# memoryModule.net
KiCad netlist of a schematic drawn in EAGLE
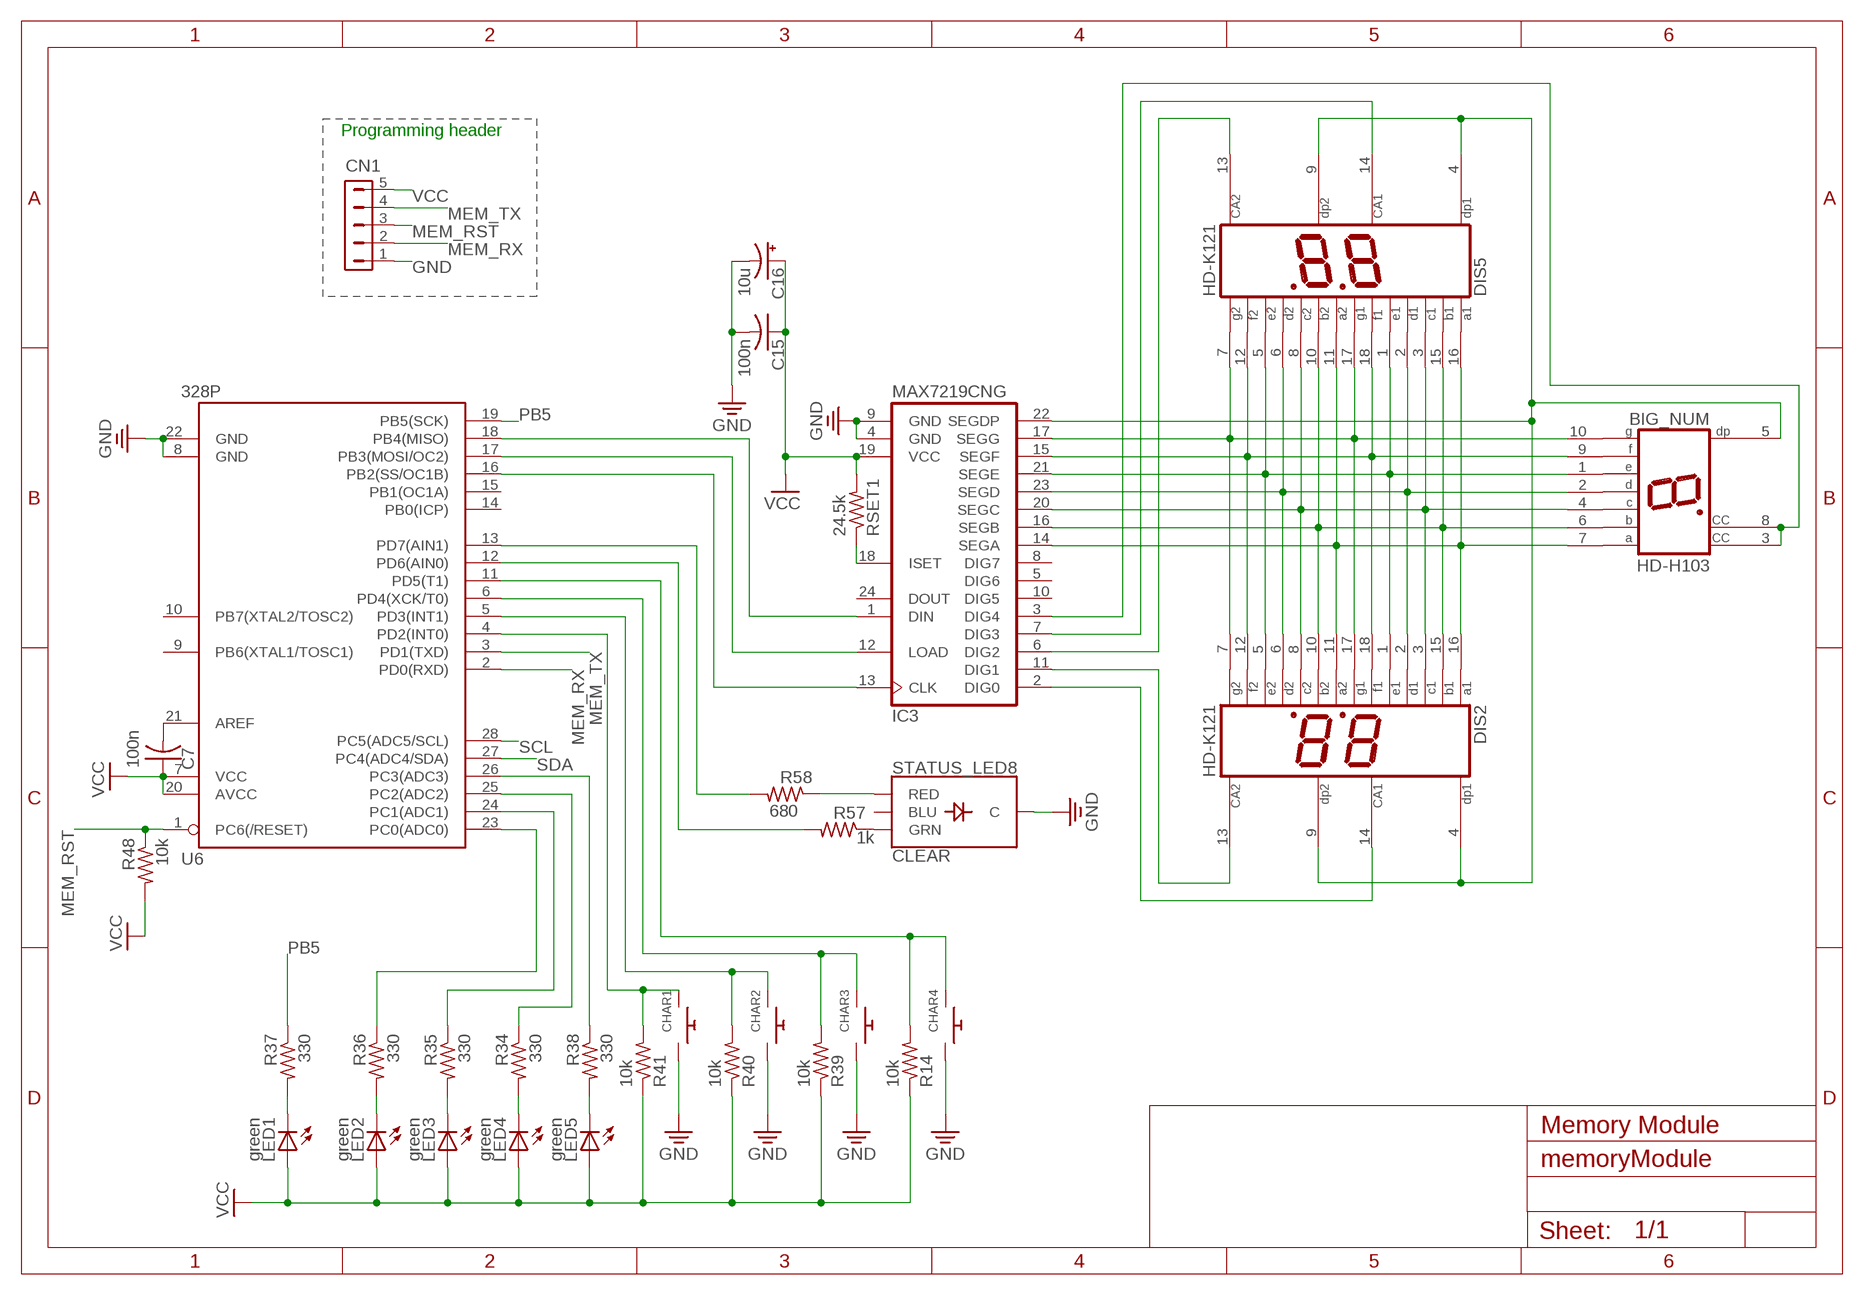
[diagram p0: schematic, sheet 1]

(export (version "E")
  (design (tool "Eeschema 10.0.6"))
  (components
    (comp (ref "BIG_NUM")
      (value "HD-H103")
      (footprint "eagle-import:HDSP-M")
      (libsource (lib "eagle-import") (part "HD-H103"))
    )
    (comp (ref "C7")
      (value "100n")
      (footprint "eagle-import:C025-024X044")
      (libsource (lib "eagle-import") (part "C-US025-024X044"))
    )
    (comp (ref "C15")
      (value "100n")
      (footprint "eagle-import:C025-024X044")
      (libsource (lib "eagle-import") (part "C-US025-024X044"))
    )
    (comp (ref "C16")
      (value "10u")
      (footprint "eagle-import:085CS_1AR")
      (libsource (lib "eagle-import") (part "CPOL-US085CS-1AR"))
    )
    (comp (ref "CHAR1")
      (value "SWITCH_PUSHBUTTONEVQ-PE")
      (footprint "eagle-import:TACT_PANA-EVQ")
      (libsource (lib "eagle-import") (part "SWITCH_PUSHBUTTONEVQ-PE"))
    )
    (comp (ref "CHAR2")
      (value "SWITCH_PUSHBUTTONEVQ-PE")
      (footprint "eagle-import:TACT_PANA-EVQ")
      (libsource (lib "eagle-import") (part "SWITCH_PUSHBUTTONEVQ-PE"))
    )
    (comp (ref "CHAR3")
      (value "SWITCH_PUSHBUTTONEVQ-PE")
      (footprint "eagle-import:TACT_PANA-EVQ")
      (libsource (lib "eagle-import") (part "SWITCH_PUSHBUTTONEVQ-PE"))
    )
    (comp (ref "CHAR4")
      (value "SWITCH_PUSHBUTTONEVQ-PE")
      (footprint "eagle-import:TACT_PANA-EVQ")
      (libsource (lib "eagle-import") (part "SWITCH_PUSHBUTTONEVQ-PE"))
    )
    (comp (ref "CN1")
      (value "HDR-1X5-SIP-100")
      (footprint "eagle-import:SIP-100-5V")
      (libsource (lib "eagle-import") (part "HDR-1X5-SIP-100"))
    )
    (comp (ref "DIS2")
      (value "HD-K121")
      (footprint "eagle-import:HDSP-R")
      (libsource (lib "eagle-import") (part "HD-K121"))
    )
    (comp (ref "DIS5")
      (value "HD-K121")
      (footprint "eagle-import:HDSP-R")
      (libsource (lib "eagle-import") (part "HD-K121"))
    )
    (comp (ref "IC3")
      (value "MAX7219CNG")
      (footprint "eagle-import:DIL24-3")
      (fields (field (name "MF") "MAXIM"))
      (libsource (lib "eagle-import") (part "MAX7219CNG"))
    )
    (comp (ref "LED1")
      (value "green")
      (footprint "eagle-import:LED5MM")
      (libsource (lib "eagle-import") (part "LED5MM"))
    )
    (comp (ref "LED2")
      (value "green")
      (footprint "eagle-import:LED5MM")
      (libsource (lib "eagle-import") (part "LED5MM"))
    )
    (comp (ref "LED3")
      (value "green")
      (footprint "eagle-import:LED5MM")
      (libsource (lib "eagle-import") (part "LED5MM"))
    )
    (comp (ref "LED4")
      (value "green")
      (footprint "eagle-import:LED5MM")
      (libsource (lib "eagle-import") (part "LED5MM"))
    )
    (comp (ref "LED5")
      (value "green")
      (footprint "eagle-import:LED5MM")
      (libsource (lib "eagle-import") (part "LED5MM"))
    )
    (comp (ref "R14")
      (value "10k")
      (footprint "eagle-import:0309_12")
      (libsource (lib "eagle-import") (part "adafruit_420_R-US_0309/12"))
    )
    (comp (ref "R34")
      (value "330")
      (footprint "eagle-import:0309_12")
      (libsource (lib "eagle-import") (part "adafruit_420_R-US_0309/12"))
    )
    (comp (ref "R35")
      (value "330")
      (footprint "eagle-import:0309_12")
      (libsource (lib "eagle-import") (part "adafruit_420_R-US_0309/12"))
    )
    (comp (ref "R36")
      (value "330")
      (footprint "eagle-import:0309_12")
      (libsource (lib "eagle-import") (part "adafruit_420_R-US_0309/12"))
    )
    (comp (ref "R37")
      (value "330")
      (footprint "eagle-import:0309_12")
      (libsource (lib "eagle-import") (part "adafruit_420_R-US_0309/12"))
    )
    (comp (ref "R38")
      (value "330")
      (footprint "eagle-import:0309_12")
      (libsource (lib "eagle-import") (part "adafruit_420_R-US_0309/12"))
    )
    (comp (ref "R39")
      (value "10k")
      (footprint "eagle-import:0309_12")
      (libsource (lib "eagle-import") (part "adafruit_420_R-US_0309/12"))
    )
    (comp (ref "R40")
      (value "10k")
      (footprint "eagle-import:0309_12")
      (libsource (lib "eagle-import") (part "adafruit_420_R-US_0309/12"))
    )
    (comp (ref "R41")
      (value "10k")
      (footprint "eagle-import:0309_12")
      (libsource (lib "eagle-import") (part "adafruit_420_R-US_0309/12"))
    )
    (comp (ref "R48")
      (value "10k")
      (footprint "eagle-import:0309_12")
      (libsource (lib "eagle-import") (part "adafruit_420_R-US_0309/12"))
    )
    (comp (ref "R57")
      (value "1k")
      (footprint "eagle-import:0805-THM")
      (libsource (lib "eagle-import") (part "FLIPFLOP-RES"))
    )
    (comp (ref "R58")
      (value "680")
      (footprint "eagle-import:0805-THM")
      (libsource (lib "eagle-import") (part "FLIPFLOP-RES"))
    )
    (comp (ref "RSET1")
      (value "24.5k")
      (footprint "eagle-import:0204_7")
      (libsource (lib "eagle-import") (part "R-US_0204/7"))
    )
    (comp (ref "STATUS_LED8")
      (value "CLEAR")
      (footprint "eagle-import:LED-RGB-THRU")
      (libsource (lib "eagle-import") (part "LED-RGB-CCCLEAR"))
    )
    (comp (ref "U6")
      (value "328P")
      (footprint "eagle-import:DIP28")
      (libsource (lib "eagle-import") (part "ATMEGA328P_PDIP"))
    )
  )
  (nets
    (net (code "1") (name "/MEM_RST") (class "Default")
      (node (ref "CN1") (pin "3") (pinfunction "3_3") (pintype "passive"))
      (node (ref "R48") (pin "1") (pinfunction "1_1") (pintype "passive"))
      (node (ref "U6") (pin "1") (pinfunction "PC6(/RESET)_1") (pintype "bidirectional"))
    )
    (net (code "2") (name "/MEM_RX") (class "Default")
      (node (ref "CN1") (pin "2") (pinfunction "2_2") (pintype "passive"))
      (node (ref "U6") (pin "2") (pinfunction "PD0(RXD)_2") (pintype "bidirectional"))
    )
    (net (code "3") (name "/MEM_TX") (class "Default")
      (node (ref "CN1") (pin "4") (pinfunction "4_4") (pintype "passive"))
      (node (ref "U6") (pin "3") (pinfunction "PD1(TXD)_3") (pintype "bidirectional"))
    )
    (net (code "4") (name "/N$114") (class "Default")
      (node (ref "R35") (pin "1") (pinfunction "1_1") (pintype "passive"))
      (node (ref "R36") (pin "1") (pinfunction "1_1") (pintype "passive"))
      (node (ref "R38") (pin "1") (pinfunction "1_1") (pintype "passive"))
      (node (ref "U6") (pin "23") (pinfunction "PC0(ADC0)_23") (pintype "bidirectional"))
      (node (ref "U6") (pin "24") (pinfunction "PC1(ADC1)_24") (pintype "bidirectional"))
      (node (ref "U6") (pin "26") (pinfunction "PC3(ADC3)_26") (pintype "bidirectional"))
    )
    (net (code "5") (name "/PB5") (class "Default")
      (node (ref "R37") (pin "1") (pinfunction "1_1") (pintype "passive"))
      (node (ref "U6") (pin "19") (pinfunction "PB5(SCK)_19") (pintype "bidirectional"))
    )
    (net (code "6") (name "/SCL") (class "Default")
      (node (ref "U6") (pin "28") (pinfunction "PC5(ADC5/SCL)_28") (pintype "bidirectional"))
    )
    (net (code "7") (name "/SDA") (class "Default")
      (node (ref "U6") (pin "27") (pinfunction "PC4(ADC4/SDA)_27") (pintype "bidirectional"))
    )
    (net (code "8") (name "GND") (class "Default")
      (node (ref "C15") (pin "2") (pinfunction "2_2") (pintype "passive"))
      (node (ref "C16") (pin "-") (pinfunction "-_-") (pintype "passive"))
      (node (ref "CHAR1") (pin "P$1") (pinfunction "P$1_P$1") (pintype "passive"))
      (node (ref "CHAR2") (pin "P$1") (pinfunction "P$1_P$1") (pintype "passive"))
      (node (ref "CHAR3") (pin "P$1") (pinfunction "P$1_P$1") (pintype "passive"))
      (node (ref "CHAR4") (pin "P$1") (pinfunction "P$1_P$1") (pintype "passive"))
      (node (ref "CN1") (pin "1") (pinfunction "1_1") (pintype "passive"))
      (node (ref "IC3") (pin "4") (pinfunction "GND_4") (pintype "power_in"))
      (node (ref "IC3") (pin "9") (pinfunction "GND_9") (pintype "power_in"))
      (node (ref "STATUS_LED8") (pin "2") (pinfunction "C_2") (pintype "bidirectional"))
      (node (ref "U6") (pin "22") (pinfunction "GND_22") (pintype "bidirectional"))
      (node (ref "U6") (pin "8") (pinfunction "GND_8") (pintype "bidirectional"))
    )
    (net (code "9") (name "Net-(BIG_NUM-A)") (class "Default")
      (node (ref "BIG_NUM") (pin "7") (pinfunction "A_7") (pintype "passive"))
      (node (ref "DIS2") (pin "11") (pinfunction "A2_11") (pintype "passive"))
      (node (ref "DIS2") (pin "16") (pinfunction "A1_16") (pintype "passive"))
      (node (ref "DIS5") (pin "11") (pinfunction "A2_11") (pintype "passive"))
      (node (ref "DIS5") (pin "16") (pinfunction "A1_16") (pintype "passive"))
      (node (ref "IC3") (pin "14") (pinfunction "SEGA_14") (pintype "output"))
    )
    (net (code "10") (name "Net-(BIG_NUM-B)") (class "Default")
      (node (ref "BIG_NUM") (pin "6") (pinfunction "B_6") (pintype "passive"))
      (node (ref "DIS2") (pin "10") (pinfunction "B2_10") (pintype "passive"))
      (node (ref "DIS2") (pin "15") (pinfunction "B1_15") (pintype "passive"))
      (node (ref "DIS5") (pin "10") (pinfunction "B2_10") (pintype "passive"))
      (node (ref "DIS5") (pin "15") (pinfunction "B1_15") (pintype "passive"))
      (node (ref "IC3") (pin "16") (pinfunction "SEGB_16") (pintype "output"))
    )
    (net (code "11") (name "Net-(BIG_NUM-C)") (class "Default")
      (node (ref "BIG_NUM") (pin "4") (pinfunction "C_4") (pintype "passive"))
      (node (ref "DIS2") (pin "3") (pinfunction "C1_3") (pintype "passive"))
      (node (ref "DIS2") (pin "8") (pinfunction "C2_8") (pintype "passive"))
      (node (ref "DIS5") (pin "3") (pinfunction "C1_3") (pintype "passive"))
      (node (ref "DIS5") (pin "8") (pinfunction "C2_8") (pintype "passive"))
      (node (ref "IC3") (pin "20") (pinfunction "SEGC_20") (pintype "output"))
    )
    (net (code "12") (name "Net-(BIG_NUM-D)") (class "Default")
      (node (ref "BIG_NUM") (pin "2") (pinfunction "D_2") (pintype "passive"))
      (node (ref "DIS2") (pin "2") (pinfunction "D1_2") (pintype "passive"))
      (node (ref "DIS2") (pin "6") (pinfunction "D2_6") (pintype "passive"))
      (node (ref "DIS5") (pin "2") (pinfunction "D1_2") (pintype "passive"))
      (node (ref "DIS5") (pin "6") (pinfunction "D2_6") (pintype "passive"))
      (node (ref "IC3") (pin "23") (pinfunction "SEGD_23") (pintype "output"))
    )
    (net (code "13") (name "Net-(BIG_NUM-DP)") (class "Default")
      (node (ref "BIG_NUM") (pin "5") (pinfunction "DP_5") (pintype "passive"))
      (node (ref "DIS2") (pin "4") (pinfunction "DP1_4") (pintype "passive"))
      (node (ref "DIS2") (pin "9") (pinfunction "DP2_9") (pintype "passive"))
      (node (ref "DIS5") (pin "4") (pinfunction "DP1_4") (pintype "passive"))
      (node (ref "DIS5") (pin "9") (pinfunction "DP2_9") (pintype "passive"))
      (node (ref "IC3") (pin "22") (pinfunction "SEGDP_22") (pintype "output"))
    )
    (net (code "14") (name "Net-(BIG_NUM-E)") (class "Default")
      (node (ref "BIG_NUM") (pin "1") (pinfunction "E_1") (pintype "passive"))
      (node (ref "DIS2") (pin "1") (pinfunction "E1_1") (pintype "passive"))
      (node (ref "DIS2") (pin "5") (pinfunction "E2_5") (pintype "passive"))
      (node (ref "DIS5") (pin "1") (pinfunction "E1_1") (pintype "passive"))
      (node (ref "DIS5") (pin "5") (pinfunction "E2_5") (pintype "passive"))
      (node (ref "IC3") (pin "21") (pinfunction "SEGE_21") (pintype "output"))
    )
    (net (code "15") (name "Net-(BIG_NUM-F)") (class "Default")
      (node (ref "BIG_NUM") (pin "9") (pinfunction "F_9") (pintype "passive"))
      (node (ref "DIS2") (pin "12") (pinfunction "F2_12") (pintype "passive"))
      (node (ref "DIS2") (pin "18") (pinfunction "F1_18") (pintype "passive"))
      (node (ref "DIS5") (pin "12") (pinfunction "F2_12") (pintype "passive"))
      (node (ref "DIS5") (pin "18") (pinfunction "F1_18") (pintype "passive"))
      (node (ref "IC3") (pin "15") (pinfunction "SEGF_15") (pintype "output"))
    )
    (net (code "16") (name "Net-(BIG_NUM-G)") (class "Default")
      (node (ref "BIG_NUM") (pin "10") (pinfunction "G_10") (pintype "passive"))
      (node (ref "DIS2") (pin "17") (pinfunction "G1_17") (pintype "passive"))
      (node (ref "DIS2") (pin "7") (pinfunction "G2_7") (pintype "passive"))
      (node (ref "DIS5") (pin "17") (pinfunction "G1_17") (pintype "passive"))
      (node (ref "DIS5") (pin "7") (pinfunction "G2_7") (pintype "passive"))
      (node (ref "IC3") (pin "17") (pinfunction "SEGG_17") (pintype "output"))
    )
    (net (code "17") (name "Net-(DIS2-CA1)") (class "Default")
      (node (ref "DIS2") (pin "14") (pinfunction "CA1_14") (pintype "passive"))
      (node (ref "IC3") (pin "2") (pinfunction "DIG0_2") (pintype "output"))
    )
    (net (code "18") (name "Net-(DIS2-CA2)") (class "Default")
      (node (ref "DIS2") (pin "13") (pinfunction "CA2_13") (pintype "passive"))
      (node (ref "IC3") (pin "11") (pinfunction "DIG1_11") (pintype "output"))
    )
    (net (code "19") (name "Net-(DIS5-CA1)") (class "Default")
      (node (ref "DIS5") (pin "14") (pinfunction "CA1_14") (pintype "passive"))
      (node (ref "IC3") (pin "7") (pinfunction "DIG3_7") (pintype "output"))
    )
    (net (code "20") (name "Net-(DIS5-CA2)") (class "Default")
      (node (ref "DIS5") (pin "13") (pinfunction "CA2_13") (pintype "passive"))
      (node (ref "IC3") (pin "6") (pinfunction "DIG2_6") (pintype "output"))
    )
    (net (code "21") (name "Net-(IC3-CLK)") (class "Default")
      (node (ref "IC3") (pin "13") (pinfunction "CLK_13") (pintype "input"))
      (node (ref "U6") (pin "16") (pinfunction "PB2(SS/OC1B)_16") (pintype "bidirectional"))
    )
    (net (code "22") (name "Net-(IC3-DIG4)") (class "Default")
      (node (ref "BIG_NUM") (pin "3") (pinfunction "CC_3") (pintype "passive"))
      (node (ref "BIG_NUM") (pin "8") (pinfunction "CC_8") (pintype "passive"))
      (node (ref "IC3") (pin "3") (pinfunction "DIG4_3") (pintype "output"))
    )
    (net (code "23") (name "Net-(IC3-DIN)") (class "Default")
      (node (ref "IC3") (pin "1") (pinfunction "DIN_1") (pintype "input"))
      (node (ref "U6") (pin "18") (pinfunction "PB4(MISO)_18") (pintype "bidirectional"))
    )
    (net (code "24") (name "Net-(IC3-ISET)") (class "Default")
      (node (ref "IC3") (pin "18") (pinfunction "ISET_18") (pintype "input"))
      (node (ref "RSET1") (pin "1") (pinfunction "1_1") (pintype "passive"))
    )
    (net (code "25") (name "Net-(IC3-LOAD)") (class "Default")
      (node (ref "IC3") (pin "12") (pinfunction "LOAD_12") (pintype "input"))
      (node (ref "U6") (pin "17") (pinfunction "PB3(MOSI/OC2)_17") (pintype "bidirectional"))
    )
    (net (code "26") (name "Net-(LED1-C)") (class "Default")
      (node (ref "LED1") (pin "K") (pinfunction "C_K") (pintype "passive"))
      (node (ref "R37") (pin "2") (pinfunction "2_2") (pintype "passive"))
    )
    (net (code "27") (name "Net-(LED2-C)") (class "Default")
      (node (ref "LED2") (pin "K") (pinfunction "C_K") (pintype "passive"))
      (node (ref "R36") (pin "2") (pinfunction "2_2") (pintype "passive"))
    )
    (net (code "28") (name "Net-(LED3-C)") (class "Default")
      (node (ref "LED3") (pin "K") (pinfunction "C_K") (pintype "passive"))
      (node (ref "R35") (pin "2") (pinfunction "2_2") (pintype "passive"))
    )
    (net (code "29") (name "Net-(LED4-C)") (class "Default")
      (node (ref "LED4") (pin "K") (pinfunction "C_K") (pintype "passive"))
      (node (ref "R34") (pin "2") (pinfunction "2_2") (pintype "passive"))
    )
    (net (code "30") (name "Net-(LED5-C)") (class "Default")
      (node (ref "LED5") (pin "K") (pinfunction "C_K") (pintype "passive"))
      (node (ref "R38") (pin "2") (pinfunction "2_2") (pintype "passive"))
    )
    (net (code "31") (name "Net-(STATUS_LED8-GRN)") (class "Default")
      (node (ref "R57") (pin "1") (pinfunction "1_1") (pintype "passive"))
      (node (ref "STATUS_LED8") (pin "3") (pinfunction "GRN_3") (pintype "bidirectional"))
    )
    (net (code "32") (name "Net-(STATUS_LED8-RED)") (class "Default")
      (node (ref "R58") (pin "1") (pinfunction "1_1") (pintype "passive"))
      (node (ref "STATUS_LED8") (pin "1") (pinfunction "RED_1") (pintype "bidirectional"))
    )
    (net (code "33") (name "Net-(U6-AREF)") (class "Default")
      (node (ref "C7") (pin "2") (pinfunction "2_2") (pintype "passive"))
      (node (ref "U6") (pin "21") (pinfunction "AREF_21") (pintype "bidirectional"))
    )
    (net (code "34") (name "Net-(U6-PC2(ADC2))") (class "Default")
      (node (ref "R34") (pin "1") (pinfunction "1_1") (pintype "passive"))
      (node (ref "U6") (pin "25") (pinfunction "PC2(ADC2)_25") (pintype "bidirectional"))
    )
    (net (code "35") (name "Net-(U6-PD2(INT0))") (class "Default")
      (node (ref "CHAR1") (pin "P$2") (pinfunction "P$2_P$2") (pintype "passive"))
      (node (ref "R41") (pin "2") (pinfunction "2_2") (pintype "passive"))
      (node (ref "U6") (pin "4") (pinfunction "PD2(INT0)_4") (pintype "bidirectional"))
    )
    (net (code "36") (name "Net-(U6-PD3(INT1))") (class "Default")
      (node (ref "CHAR2") (pin "P$2") (pinfunction "P$2_P$2") (pintype "passive"))
      (node (ref "R40") (pin "2") (pinfunction "2_2") (pintype "passive"))
      (node (ref "U6") (pin "5") (pinfunction "PD3(INT1)_5") (pintype "bidirectional"))
    )
    (net (code "37") (name "Net-(U6-PD4(XCK{slash}T0))") (class "Default")
      (node (ref "CHAR3") (pin "P$2") (pinfunction "P$2_P$2") (pintype "passive"))
      (node (ref "R39") (pin "2") (pinfunction "2_2") (pintype "passive"))
      (node (ref "U6") (pin "6") (pinfunction "PD4(XCK/T0)_6") (pintype "bidirectional"))
    )
    (net (code "38") (name "Net-(U6-PD5(T1))") (class "Default")
      (node (ref "CHAR4") (pin "P$2") (pinfunction "P$2_P$2") (pintype "passive"))
      (node (ref "R14") (pin "2") (pinfunction "2_2") (pintype "passive"))
      (node (ref "U6") (pin "11") (pinfunction "PD5(T1)_11") (pintype "bidirectional"))
    )
    (net (code "39") (name "Net-(U6-PD6(AIN0))") (class "Default")
      (node (ref "R57") (pin "2") (pinfunction "2_2") (pintype "passive"))
      (node (ref "U6") (pin "12") (pinfunction "PD6(AIN0)_12") (pintype "bidirectional"))
    )
    (net (code "40") (name "Net-(U6-PD7(AIN1))") (class "Default")
      (node (ref "R58") (pin "2") (pinfunction "2_2") (pintype "passive"))
      (node (ref "U6") (pin "13") (pinfunction "PD7(AIN1)_13") (pintype "bidirectional"))
    )
    (net (code "41") (name "VCC") (class "Default")
      (node (ref "C15") (pin "1") (pinfunction "1_1") (pintype "passive"))
      (node (ref "C16") (pin "+") (pinfunction "+_+") (pintype "passive"))
      (node (ref "C7") (pin "1") (pinfunction "1_1") (pintype "passive"))
      (node (ref "CN1") (pin "5") (pinfunction "5_5") (pintype "passive"))
      (node (ref "IC3") (pin "19") (pinfunction "VCC_19") (pintype "power_in"))
      (node (ref "LED1") (pin "A") (pinfunction "A_A") (pintype "passive"))
      (node (ref "LED2") (pin "A") (pinfunction "A_A") (pintype "passive"))
      (node (ref "LED3") (pin "A") (pinfunction "A_A") (pintype "passive"))
      (node (ref "LED4") (pin "A") (pinfunction "A_A") (pintype "passive"))
      (node (ref "LED5") (pin "A") (pinfunction "A_A") (pintype "passive"))
      (node (ref "R14") (pin "1") (pinfunction "1_1") (pintype "passive"))
      (node (ref "R39") (pin "1") (pinfunction "1_1") (pintype "passive"))
      (node (ref "R40") (pin "1") (pinfunction "1_1") (pintype "passive"))
      (node (ref "R41") (pin "1") (pinfunction "1_1") (pintype "passive"))
      (node (ref "R48") (pin "2") (pinfunction "2_2") (pintype "passive"))
      (node (ref "RSET1") (pin "2") (pinfunction "2_2") (pintype "passive"))
      (node (ref "U6") (pin "20") (pinfunction "AVCC_20") (pintype "bidirectional"))
      (node (ref "U6") (pin "7") (pinfunction "VCC_7") (pintype "bidirectional"))
    )
    (net (code "42") (name "unconnected-(IC3-DIG5-Pad10)") (class "Default")
      (node (ref "IC3") (pin "10") (pinfunction "DIG5_10") (pintype "output"))
    )
    (net (code "43") (name "unconnected-(IC3-DIG6-Pad5)") (class "Default")
      (node (ref "IC3") (pin "5") (pinfunction "DIG6_5") (pintype "output"))
    )
    (net (code "44") (name "unconnected-(IC3-DIG7-Pad8)") (class "Default")
      (node (ref "IC3") (pin "8") (pinfunction "DIG7_8") (pintype "output"))
    )
    (net (code "45") (name "unconnected-(IC3-DOUT-Pad24)") (class "Default")
      (node (ref "IC3") (pin "24") (pinfunction "DOUT_24") (pintype "output"))
    )
    (net (code "46") (name "unconnected-(STATUS_LED8-BLU-Pad4)") (class "Default")
      (node (ref "STATUS_LED8") (pin "4") (pinfunction "BLU_4") (pintype "bidirectional"))
    )
    (net (code "47") (name "unconnected-(U6-PB0(ICP)-Pad14)") (class "Default")
      (node (ref "U6") (pin "14") (pinfunction "PB0(ICP)_14") (pintype "bidirectional"))
    )
    (net (code "48") (name "unconnected-(U6-PB1(OC1A)-Pad15)") (class "Default")
      (node (ref "U6") (pin "15") (pinfunction "PB1(OC1A)_15") (pintype "bidirectional"))
    )
    (net (code "49") (name "unconnected-(U6-PB6(XTAL1{slash}TOSC1)-Pad9)") (class "Default")
      (node (ref "U6") (pin "9") (pinfunction "PB6(XTAL1/TOSC1)_9") (pintype "bidirectional"))
    )
    (net (code "50") (name "unconnected-(U6-PB7(XTAL2{slash}TOSC2)-Pad10)") (class "Default")
      (node (ref "U6") (pin "10") (pinfunction "PB7(XTAL2/TOSC2)_10") (pintype "bidirectional"))
    )
  )
)
